# Sheet1.net
KiCad netlist of a schematic drawn in Altium Designer
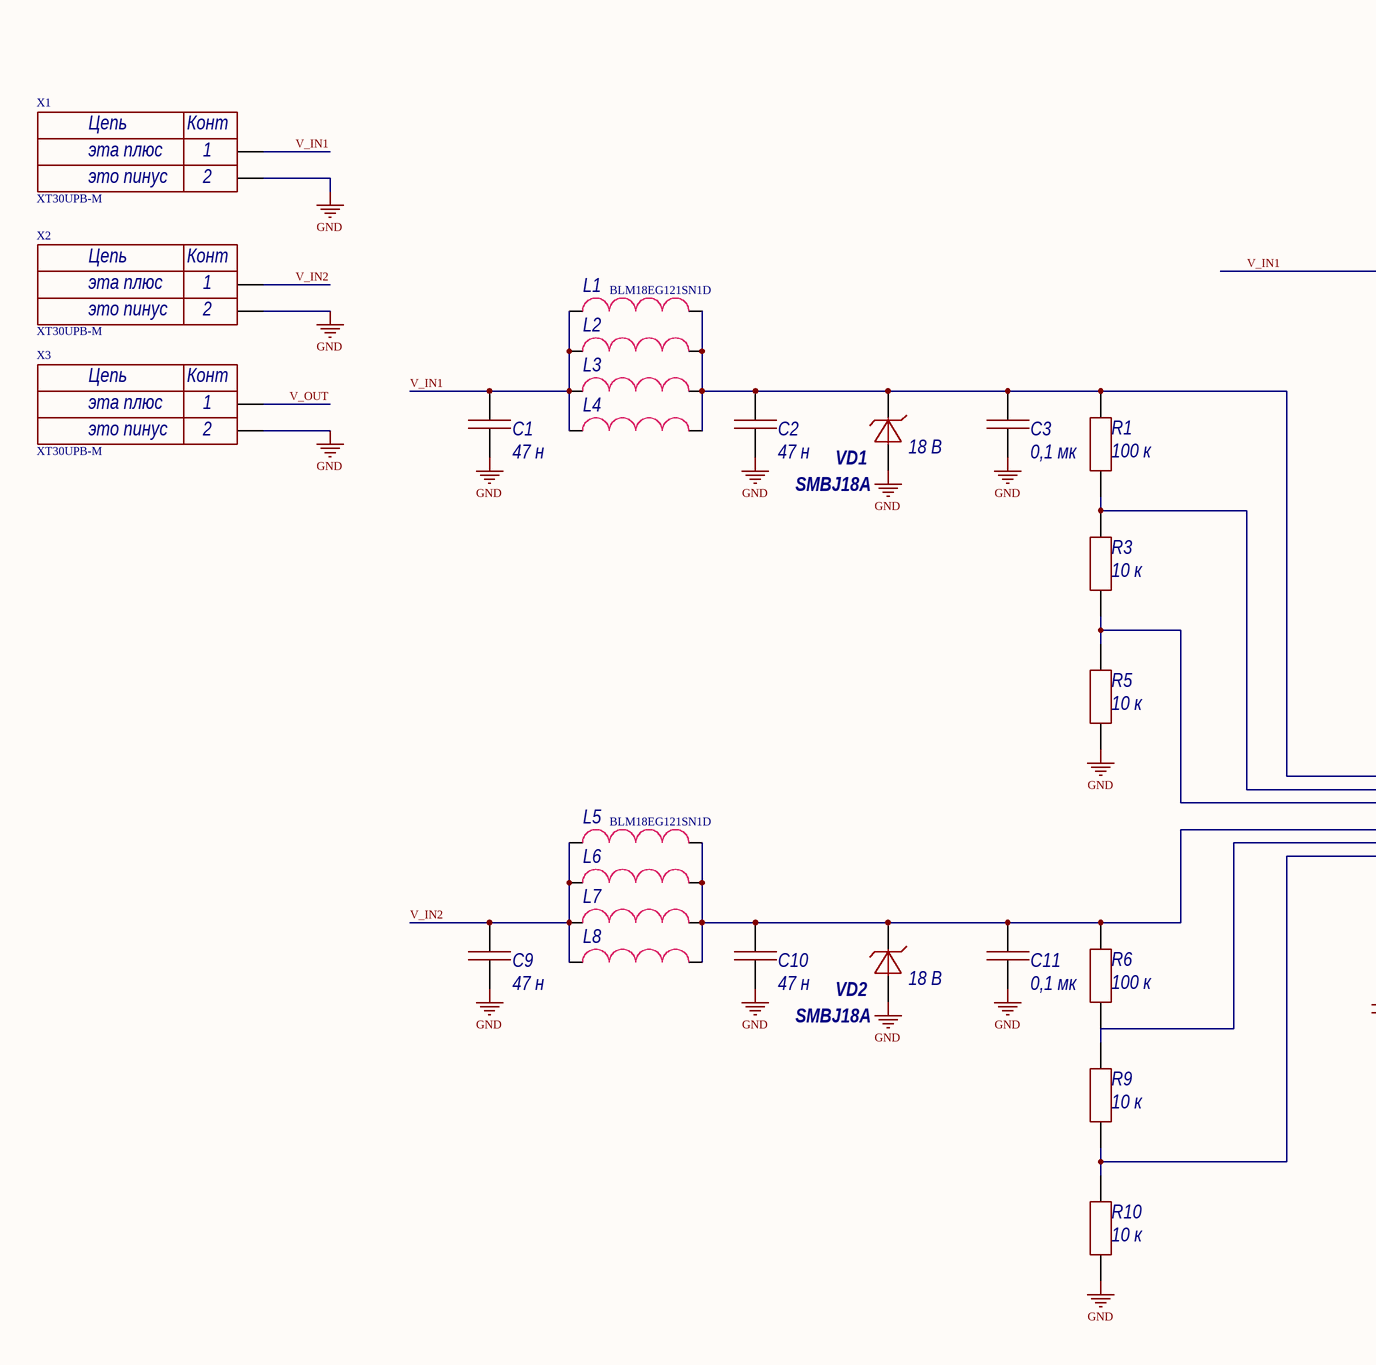
[diagram p0: Sheet1.SchDoc, left]
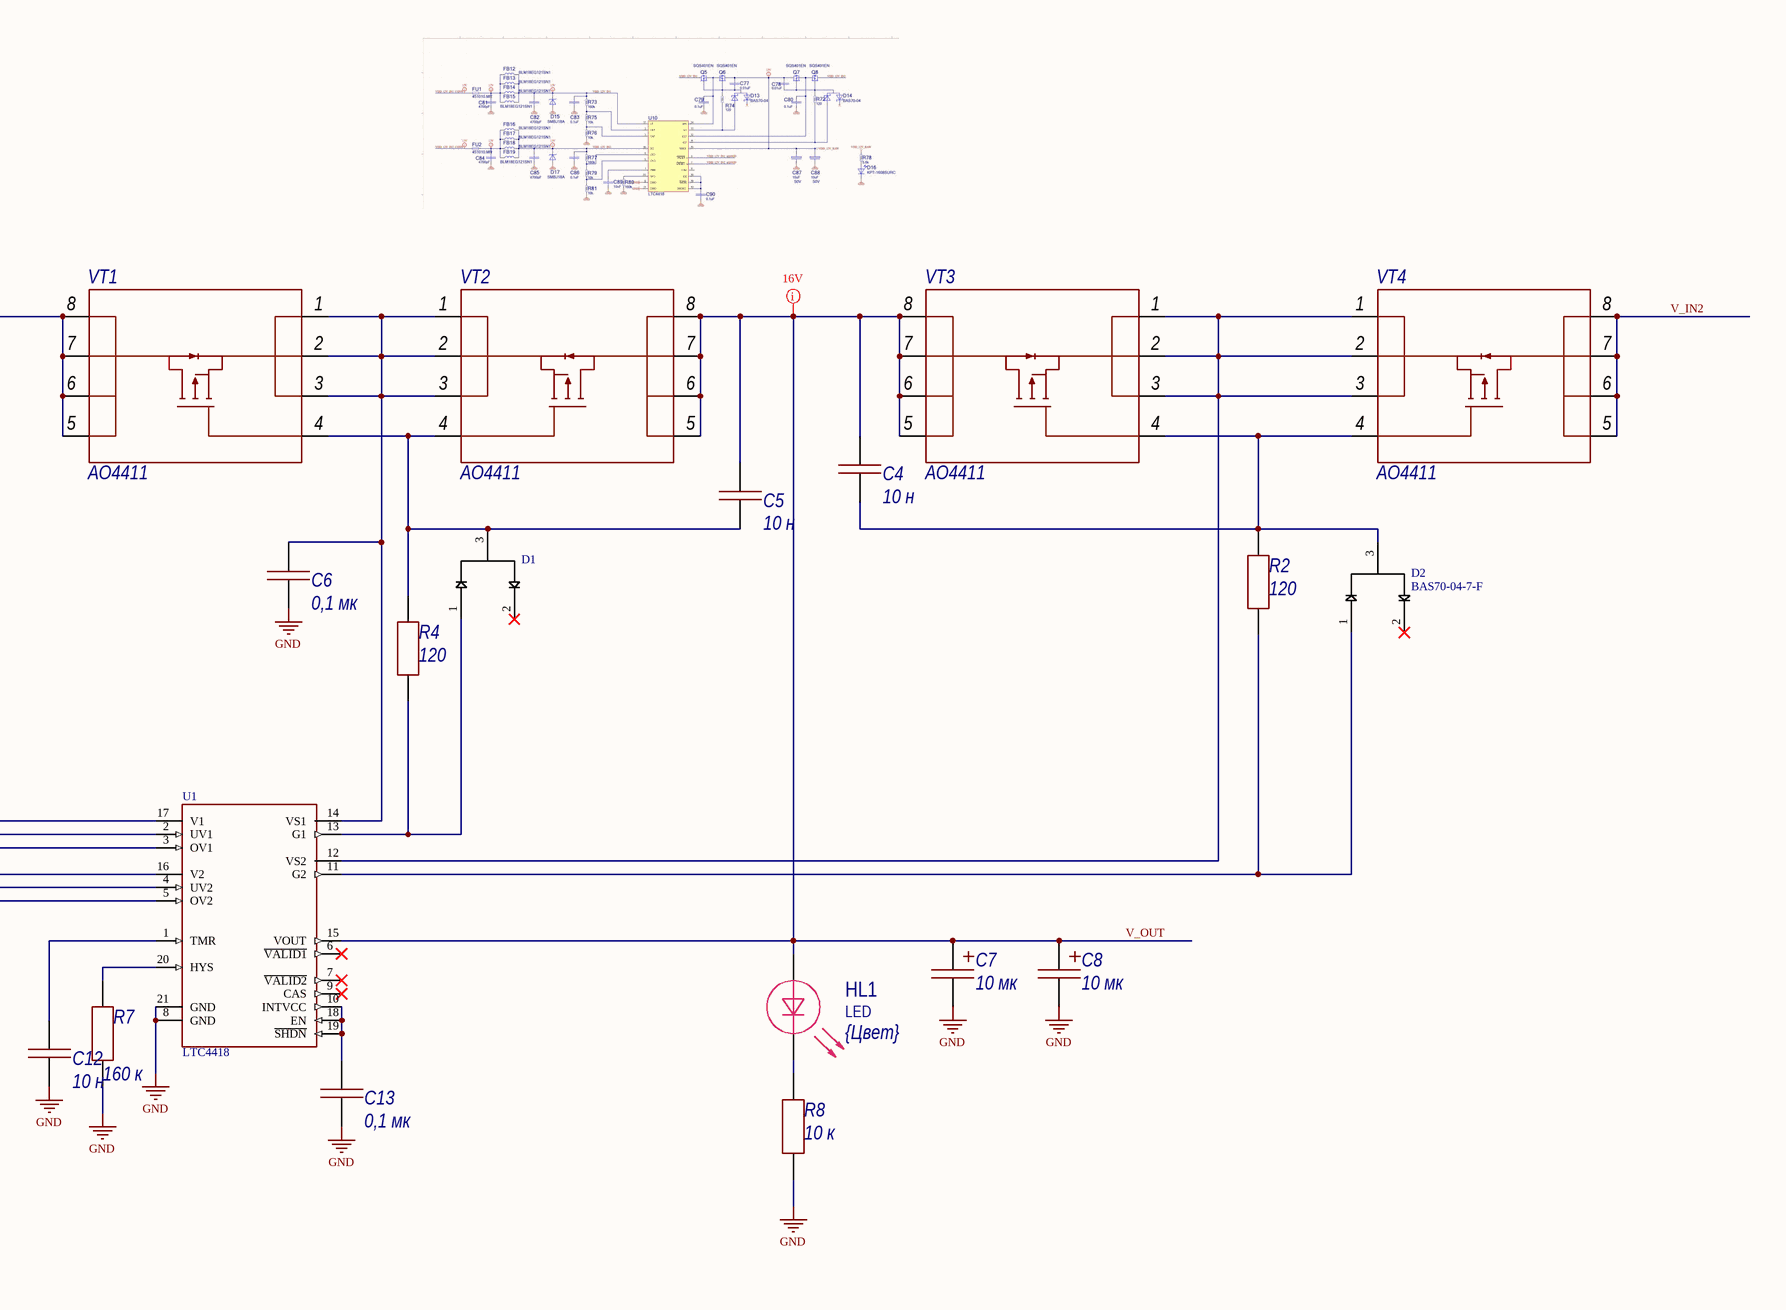
[diagram p1: Sheet1.SchDoc, right]

(export (version "E")
  (design (tool "Eeschema 10.0.6"))
  (components
    (comp (ref "C1")
      (value "47 н")
      (footprint "0603C")
      (description "Конденсатор")
      (fields (field (name "PART NUMBER") "Capacitor_47n_10_50V_X7R_0603C") (field (name "TOLERANCE") "0,1"))
      (libsource (lib "Hydrolib") (part "Capacitor"))
    )
    (comp (ref "C2")
      (value "47 н")
      (footprint "0603C")
      (description "Конденсатор")
      (fields (field (name "PART NUMBER") "Capacitor_47n_10_50V_X7R_0603C") (field (name "TOLERANCE") "0,1"))
      (libsource (lib "Hydrolib") (part "Capacitor"))
    )
    (comp (ref "C3")
      (value "0,1 мк")
      (footprint "0603C")
      (description "Конденсатор")
      (fields (field (name "PART NUMBER") "Capacitor_0,1u_10_50V_X7R_0603C") (field (name "TOLERANCE") "0,1"))
      (libsource (lib "Hydrolib") (part "Capacitor"))
    )
    (comp (ref "C4")
      (value "10 н")
      (footprint "0603C")
      (description "Конденсатор")
      (fields (field (name "PART NUMBER") "Capacitor_10n_10_50V_X7R_0603C") (field (name "TOLERANCE") "0,1"))
      (libsource (lib "Hydrolib") (part "Capacitor"))
    )
    (comp (ref "C5")
      (value "10 н")
      (footprint "0603C")
      (description "Конденсатор")
      (fields (field (name "PART NUMBER") "Capacitor_10n_10_50V_X7R_0603C") (field (name "TOLERANCE") "0,1"))
      (libsource (lib "Hydrolib") (part "Capacitor"))
    )
    (comp (ref "C6")
      (value "0,1 мк")
      (footprint "0603C")
      (description "Конденсатор")
      (fields (field (name "PART NUMBER") "Capacitor_0,1u_10_50V_X7R_0603C") (field (name "TOLERANCE") "0,1"))
      (libsource (lib "Hydrolib") (part "Capacitor"))
    )
    (comp (ref "C7")
      (value "10 мк")
      (footprint "TC_A")
      (description "Танталовый конденсатор")
      (fields (field (name "PART NUMBER") "Capacitor_10u_10_50V_TC_A") (field (name "TOLERANCE") "0,1"))
      (libsource (lib "Hydrolib") (part "Capacitor_polar"))
    )
    (comp (ref "C8")
      (value "10 мк")
      (footprint "TC_A")
      (description "Танталовый конденсатор")
      (fields (field (name "PART NUMBER") "Capacitor_10u_10_50V_TC_A") (field (name "TOLERANCE") "0,1"))
      (libsource (lib "Hydrolib") (part "Capacitor_polar"))
    )
    (comp (ref "C9")
      (value "47 н")
      (footprint "0603C")
      (description "Конденсатор")
      (fields (field (name "PART NUMBER") "Capacitor_47n_10_50V_X7R_0603C") (field (name "TOLERANCE") "0,1"))
      (libsource (lib "Hydrolib") (part "Capacitor"))
    )
    (comp (ref "C10")
      (value "47 н")
      (footprint "0603C")
      (description "Конденсатор")
      (fields (field (name "PART NUMBER") "Capacitor_47n_10_50V_X7R_0603C") (field (name "TOLERANCE") "0,1"))
      (libsource (lib "Hydrolib") (part "Capacitor"))
    )
    (comp (ref "C11")
      (value "0,1 мк")
      (footprint "0603C")
      (description "Конденсатор")
      (fields (field (name "PART NUMBER") "Capacitor_0,1u_10_50V_X7R_0603C") (field (name "TOLERANCE") "0,1"))
      (libsource (lib "Hydrolib") (part "Capacitor"))
    )
    (comp (ref "C12")
      (value "10 н")
      (footprint "0603C")
      (description "Конденсатор")
      (fields (field (name "PART NUMBER") "Capacitor_10n_10_50V_X7R_0603C") (field (name "TOLERANCE") "0,1"))
      (libsource (lib "Hydrolib") (part "Capacitor"))
    )
    (comp (ref "C13")
      (value "0,1 мк")
      (footprint "0603C")
      (description "Конденсатор")
      (fields (field (name "PART NUMBER") "Capacitor_0,1u_10_50V_X7R_0603C") (field (name "TOLERANCE") "0,1"))
      (libsource (lib "Hydrolib") (part "Capacitor"))
    )
    (comp (ref "D1")
      (value "~")
      (footprint "SOT23")
      (fields (field (name "MP") "BAS70-04-7-F") (field (name "MF") "Diodes Inc."))
      (libsource (lib "Hydrolib") (part "BAS70-04-7-F"))
    )
    (comp (ref "D2")
      (value "BAS70-04-7-F")
      (footprint "SOT23")
      (fields (field (name "MF") "Diodes Inc."))
      (libsource (lib "Hydrolib") (part "BAS70-04-7-F"))
    )
    (comp (ref "HL1")
      (value "LED")
      (footprint "0805D")
      (description "Светодиод")
      (fields (field (name "COLOR") "{Цвет}"))
      (libsource (lib "Hydrolib") (part "LED"))
    )
    (comp (ref "L1")
      (value "BLM18EG121SN1D")
      (footprint "0603L")
      (description "Катушка индуктивности")
      (fields (field (name "PART NUMBER") "Inductance"))
      (libsource (lib "Hydrolib") (part "Inductance"))
    )
    (comp (ref "L2")
      (value "Inductance")
      (footprint "0603L")
      (description "Катушка индуктивности")
      (libsource (lib "Hydrolib") (part "Inductance"))
    )
    (comp (ref "L3")
      (value "Inductance")
      (footprint "0603L")
      (description "Катушка индуктивности")
      (libsource (lib "Hydrolib") (part "Inductance"))
    )
    (comp (ref "L4")
      (value "Inductance")
      (footprint "0603L")
      (description "Катушка индуктивности")
      (libsource (lib "Hydrolib") (part "Inductance"))
    )
    (comp (ref "L5")
      (value "BLM18EG121SN1D")
      (footprint "0603L")
      (description "Катушка индуктивности")
      (fields (field (name "PART NUMBER") "Inductance"))
      (libsource (lib "Hydrolib") (part "Inductance"))
    )
    (comp (ref "L6")
      (value "Inductance")
      (footprint "0603L")
      (description "Катушка индуктивности")
      (libsource (lib "Hydrolib") (part "Inductance"))
    )
    (comp (ref "L7")
      (value "Inductance")
      (footprint "0603L")
      (description "Катушка индуктивности")
      (libsource (lib "Hydrolib") (part "Inductance"))
    )
    (comp (ref "L8")
      (value "Inductance")
      (footprint "0603L")
      (description "Катушка индуктивности")
      (libsource (lib "Hydrolib") (part "Inductance"))
    )
    (comp (ref "R1")
      (value "100 к")
      (footprint "0603R")
      (description "Резистор номиналом 100 кОм и точностью 1%")
      (fields (field (name "PART NUMBER") "Resistor_100k_1_0603") (field (name "TOLERANCE") "1%"))
      (libsource (lib "Hydrolib") (part "Resistor"))
    )
    (comp (ref "R2")
      (value "120")
      (footprint "0603R")
      (description "Резистор номиналом 120 Ом и точностью 1%")
      (fields (field (name "PART NUMBER") "Resistor_120_1_0603") (field (name "TOLERANCE") "1%"))
      (libsource (lib "Hydrolib") (part "Resistor"))
    )
    (comp (ref "R3")
      (value "10 к")
      (footprint "0603R")
      (description "Резистор номиналом 10 кОм и точностью 1%")
      (fields (field (name "PART NUMBER") "Resistor_10k_1_0603") (field (name "TOLERANCE") "1%"))
      (libsource (lib "Hydrolib") (part "Resistor"))
    )
    (comp (ref "R4")
      (value "120")
      (footprint "0603R")
      (description "Резистор номиналом 120 Ом и точностью 1%")
      (fields (field (name "PART NUMBER") "Resistor_120_1_0603") (field (name "TOLERANCE") "1%"))
      (libsource (lib "Hydrolib") (part "Resistor"))
    )
    (comp (ref "R5")
      (value "10 к")
      (footprint "0603R")
      (description "Резистор номиналом 10 кОм и точностью 1%")
      (fields (field (name "PART NUMBER") "Resistor_10k_1_0603") (field (name "TOLERANCE") "1%"))
      (libsource (lib "Hydrolib") (part "Resistor"))
    )
    (comp (ref "R6")
      (value "100 к")
      (footprint "0603R")
      (description "Резистор номиналом 100 кОм и точностью 1%")
      (fields (field (name "PART NUMBER") "Resistor_100k_1_0603") (field (name "TOLERANCE") "1%"))
      (libsource (lib "Hydrolib") (part "Resistor"))
    )
    (comp (ref "R7")
      (value "160 к")
      (footprint "0603R")
      (description "Резистор номиналом 160 кОм и точностью 1%")
      (fields (field (name "PART NUMBER") "Resistor_160k_1_0603") (field (name "TOLERANCE") "1%"))
      (libsource (lib "Hydrolib") (part "Resistor"))
    )
    (comp (ref "R8")
      (value "10 к")
      (footprint "0603R")
      (description "Резистор номиналом 10 кОм и точностью 1%")
      (fields (field (name "PART NUMBER") "Resistor_10k_1_0603") (field (name "TOLERANCE") "1%"))
      (libsource (lib "Hydrolib") (part "Resistor"))
    )
    (comp (ref "R9")
      (value "10 к")
      (footprint "0603R")
      (description "Резистор номиналом 10 кОм и точностью 1%")
      (fields (field (name "PART NUMBER") "Resistor_10k_1_0603") (field (name "TOLERANCE") "1%"))
      (libsource (lib "Hydrolib") (part "Resistor"))
    )
    (comp (ref "R10")
      (value "10 к")
      (footprint "0603R")
      (description "Резистор номиналом 10 кОм и точностью 1%")
      (fields (field (name "PART NUMBER") "Resistor_10k_1_0603") (field (name "TOLERANCE") "1%"))
      (libsource (lib "Hydrolib") (part "Resistor"))
    )
    (comp (ref "U1")
      (value "LTC4418")
      (footprint "QFN50")
      (fields (field (name "MF") "Analog Devices") (field (name "MP") "LTC4418IUF#PBF"))
      (libsource (lib "Hydrolib") (part "LTC4418"))
    )
    (comp (ref "VD1")
      (value "SMBJ18A")
      (footprint "SMB")
      (description "Защитный диод на 18 В, рассеиваемая мощность 600 Вт")
      (fields (field (name "ALTIUM_VALUE") "18 В"))
      (libsource (lib "Hydrolib") (part "TVS_1_1dir"))
    )
    (comp (ref "VD2")
      (value "SMBJ18A")
      (footprint "SMB")
      (description "Защитный диод на 18 В, рассеиваемая мощность 600 Вт")
      (fields (field (name "ALTIUM_VALUE") "18 В"))
      (libsource (lib "Hydrolib") (part "TVS_1_1dir"))
    )
    (comp (ref "VT1")
      (value "AO4411")
      (footprint "SOIC-8")
      (description "P-канальный MOSFET")
      (libsource (lib "") (part "MOSFET_P-channel_8pin_1"))
    )
    (comp (ref "VT2")
      (value "AO4411")
      (footprint "SOIC-8")
      (description "P-канальный MOSFET")
      (libsource (lib "Hydrolib") (part "MOSFET_P-channel_8pin"))
    )
    (comp (ref "VT3")
      (value "AO4411")
      (footprint "SOIC-8")
      (description "P-канальный MOSFET")
      (libsource (lib "") (part "MOSFET_P-channel_8pin_1"))
    )
    (comp (ref "VT4")
      (value "AO4411")
      (footprint "SOIC-8")
      (description "P-канальный MOSFET")
      (libsource (lib "Hydrolib") (part "MOSFET_P-channel_8pin"))
    )
    (comp (ref "X1")
      (value "XT30UPB-M")
      (footprint "XT30UPB-M")
      (description "2-пиновый разъем с ключом")
      (fields (field (name "VALUE2") "это пинус") (field (name "VALUE1") "эта плюс"))
      (libsource (lib "Hydrolib") (part "Polar_Conn"))
    )
    (comp (ref "X2")
      (value "XT30UPB-M")
      (footprint "XT30UPB-M")
      (description "2-пиновый разъем с ключом")
      (fields (field (name "VALUE2") "это пинус") (field (name "VALUE1") "эта плюс"))
      (libsource (lib "Hydrolib") (part "Polar_Conn"))
    )
    (comp (ref "X3")
      (value "XT30UPB-M")
      (footprint "XT30UPB-M")
      (description "2-пиновый разъем с ключом")
      (fields (field (name "VALUE2") "это пинус") (field (name "VALUE1") "эта плюс"))
      (libsource (lib "Hydrolib") (part "Polar_Conn"))
    )
  )
  (nets
    (net (code "1") (name "/V_IN1") (class "Default")
      (node (ref "C1") (pin "2") (pinfunction "2_2") (pintype "passive"))
      (node (ref "L1") (pin "1") (pinfunction "1_1") (pintype "passive"))
      (node (ref "L2") (pin "1") (pinfunction "1_1") (pintype "passive"))
      (node (ref "L3") (pin "1") (pinfunction "1_1") (pintype "passive"))
      (node (ref "L4") (pin "1") (pinfunction "1_1") (pintype "passive"))
      (node (ref "VT1") (pin "5") (pinfunction "5_5") (pintype "passive"))
      (node (ref "VT1") (pin "6") (pinfunction "6_6") (pintype "passive"))
      (node (ref "VT1") (pin "7") (pinfunction "7_7") (pintype "passive"))
      (node (ref "VT1") (pin "8") (pinfunction "8_8") (pintype "passive"))
      (node (ref "X1") (pin "P") (pinfunction "P_P") (pintype "passive"))
    )
    (net (code "2") (name "/V_IN2") (class "Default")
      (node (ref "C9") (pin "2") (pinfunction "2_2") (pintype "passive"))
      (node (ref "L5") (pin "1") (pinfunction "1_1") (pintype "passive"))
      (node (ref "L6") (pin "1") (pinfunction "1_1") (pintype "passive"))
      (node (ref "L7") (pin "1") (pinfunction "1_1") (pintype "passive"))
      (node (ref "L8") (pin "1") (pinfunction "1_1") (pintype "passive"))
      (node (ref "VT4") (pin "5") (pinfunction "5_5") (pintype "passive"))
      (node (ref "VT4") (pin "6") (pinfunction "6_6") (pintype "passive"))
      (node (ref "VT4") (pin "7") (pinfunction "7_7") (pintype "passive"))
      (node (ref "VT4") (pin "8") (pinfunction "8_8") (pintype "passive"))
      (node (ref "X2") (pin "P") (pinfunction "P_P") (pintype "passive"))
    )
    (net (code "3") (name "/V_OUT") (class "Default")
      (node (ref "C4") (pin "2") (pinfunction "2_2") (pintype "passive"))
      (node (ref "C5") (pin "2") (pinfunction "2_2") (pintype "passive"))
      (node (ref "C7") (pin "1") (pinfunction "1_1") (pintype "passive"))
      (node (ref "C8") (pin "1") (pinfunction "1_1") (pintype "passive"))
      (node (ref "HL1") (pin "1") (pinfunction "1_1") (pintype "passive"))
      (node (ref "U1") (pin "15") (pinfunction "VOUT_15") (pintype "output"))
      (node (ref "VT2") (pin "5") (pinfunction "5_5") (pintype "passive"))
      (node (ref "VT2") (pin "6") (pinfunction "6_6") (pintype "passive"))
      (node (ref "VT2") (pin "7") (pinfunction "7_7") (pintype "passive"))
      (node (ref "VT2") (pin "8") (pinfunction "8_8") (pintype "passive"))
      (node (ref "VT3") (pin "5") (pinfunction "5_5") (pintype "passive"))
      (node (ref "VT3") (pin "6") (pinfunction "6_6") (pintype "passive"))
      (node (ref "VT3") (pin "7") (pinfunction "7_7") (pintype "passive"))
      (node (ref "VT3") (pin "8") (pinfunction "8_8") (pintype "passive"))
      (node (ref "X3") (pin "P") (pinfunction "P_P") (pintype "passive"))
    )
    (net (code "4") (name "GND") (class "Default")
      (node (ref "C1") (pin "1") (pinfunction "1_1") (pintype "passive"))
      (node (ref "C10") (pin "1") (pinfunction "1_1") (pintype "passive"))
      (node (ref "C11") (pin "1") (pinfunction "1_1") (pintype "passive"))
      (node (ref "C12") (pin "1") (pinfunction "1_1") (pintype "passive"))
      (node (ref "C13") (pin "1") (pinfunction "1_1") (pintype "passive"))
      (node (ref "C2") (pin "1") (pinfunction "1_1") (pintype "passive"))
      (node (ref "C3") (pin "1") (pinfunction "1_1") (pintype "passive"))
      (node (ref "C6") (pin "1") (pinfunction "1_1") (pintype "passive"))
      (node (ref "C7") (pin "2") (pinfunction "2_2") (pintype "passive"))
      (node (ref "C8") (pin "2") (pinfunction "2_2") (pintype "passive"))
      (node (ref "C9") (pin "1") (pinfunction "1_1") (pintype "passive"))
      (node (ref "R10") (pin "1") (pinfunction "1_1") (pintype "passive"))
      (node (ref "R5") (pin "1") (pinfunction "1_1") (pintype "passive"))
      (node (ref "R7") (pin "1") (pinfunction "1_1") (pintype "passive"))
      (node (ref "R8") (pin "1") (pinfunction "1_1") (pintype "passive"))
      (node (ref "U1") (pin "21") (pinfunction "GND_21") (pintype "power_in"))
      (node (ref "U1") (pin "8") (pinfunction "GND_8") (pintype "power_in"))
      (node (ref "VD1") (pin "1") (pinfunction "1_1") (pintype "passive"))
      (node (ref "VD2") (pin "1") (pinfunction "1_1") (pintype "passive"))
      (node (ref "X1") (pin "N") (pinfunction "N_N") (pintype "passive"))
      (node (ref "X2") (pin "N") (pinfunction "N_N") (pintype "passive"))
      (node (ref "X3") (pin "N") (pinfunction "N_N") (pintype "passive"))
    )
    (net (code "5") (name "Net-(C4-Pad1)") (class "Default")
      (node (ref "C4") (pin "1") (pinfunction "1_1") (pintype "passive"))
      (node (ref "D2") (pin "3") (pinfunction "3_3") (pintype "passive"))
      (node (ref "R2") (pin "2") (pinfunction "2_2") (pintype "passive"))
      (node (ref "VT3") (pin "4") (pinfunction "4_4") (pintype "passive"))
      (node (ref "VT4") (pin "4") (pinfunction "4_4") (pintype "passive"))
    )
    (net (code "6") (name "Net-(C5-Pad1)") (class "Default")
      (node (ref "C5") (pin "1") (pinfunction "1_1") (pintype "passive"))
      (node (ref "D1") (pin "3") (pinfunction "3_3") (pintype "passive"))
      (node (ref "R4") (pin "2") (pinfunction "2_2") (pintype "passive"))
      (node (ref "VT1") (pin "4") (pinfunction "4_4") (pintype "passive"))
      (node (ref "VT2") (pin "4") (pinfunction "4_4") (pintype "passive"))
    )
    (net (code "7") (name "Net-(HL1-Pad2)") (class "Default")
      (node (ref "HL1") (pin "2") (pinfunction "2_2") (pintype "passive"))
      (node (ref "R8") (pin "2") (pinfunction "2_2") (pintype "passive"))
    )
    (net (code "8") (name "Net-(U1-EN)") (class "Default")
      (node (ref "C13") (pin "2") (pinfunction "2_2") (pintype "passive"))
      (node (ref "U1") (pin "10") (pinfunction "INTVCC_10") (pintype "output"))
      (node (ref "U1") (pin "18") (pinfunction "EN_18") (pintype "input"))
      (node (ref "U1") (pin "19") (pinfunction "~{SHDN}_19") (pintype "input"))
    )
    (net (code "9") (name "Net-(U1-G1)") (class "Default")
      (node (ref "D1") (pin "1") (pinfunction "1_1") (pintype "passive"))
      (node (ref "R4") (pin "1") (pinfunction "1_1") (pintype "passive"))
      (node (ref "U1") (pin "13") (pinfunction "G1_13") (pintype "output"))
    )
    (net (code "10") (name "Net-(U1-G2)") (class "Default")
      (node (ref "D2") (pin "1") (pinfunction "1_1") (pintype "passive"))
      (node (ref "R2") (pin "1") (pinfunction "1_1") (pintype "passive"))
      (node (ref "U1") (pin "11") (pinfunction "G2_11") (pintype "output"))
    )
    (net (code "11") (name "Net-(U1-HYS)") (class "Default")
      (node (ref "R7") (pin "2") (pinfunction "2_2") (pintype "passive"))
      (node (ref "U1") (pin "20") (pinfunction "HYS_20") (pintype "input"))
    )
    (net (code "12") (name "Net-(U1-OV1)") (class "Default")
      (node (ref "R3") (pin "1") (pinfunction "1_1") (pintype "passive"))
      (node (ref "R5") (pin "2") (pinfunction "2_2") (pintype "passive"))
      (node (ref "U1") (pin "3") (pinfunction "OV1_3") (pintype "input"))
    )
    (net (code "13") (name "Net-(U1-OV2)") (class "Default")
      (node (ref "R10") (pin "2") (pinfunction "2_2") (pintype "passive"))
      (node (ref "R9") (pin "1") (pinfunction "1_1") (pintype "passive"))
      (node (ref "U1") (pin "5") (pinfunction "OV2_5") (pintype "input"))
    )
    (net (code "14") (name "Net-(U1-TMR)") (class "Default")
      (node (ref "C12") (pin "2") (pinfunction "2_2") (pintype "passive"))
      (node (ref "U1") (pin "1") (pinfunction "TMR_1") (pintype "input"))
    )
    (net (code "15") (name "Net-(U1-UV1)") (class "Default")
      (node (ref "R1") (pin "1") (pinfunction "1_1") (pintype "passive"))
      (node (ref "R3") (pin "2") (pinfunction "2_2") (pintype "passive"))
      (node (ref "U1") (pin "2") (pinfunction "UV1_2") (pintype "input"))
    )
    (net (code "16") (name "Net-(U1-UV2)") (class "Default")
      (node (ref "R6") (pin "1") (pinfunction "1_1") (pintype "passive"))
      (node (ref "R9") (pin "2") (pinfunction "2_2") (pintype "passive"))
      (node (ref "U1") (pin "4") (pinfunction "UV2_4") (pintype "input"))
    )
    (net (code "17") (name "Net-(U1-V1)") (class "Default")
      (node (ref "C2") (pin "2") (pinfunction "2_2") (pintype "passive"))
      (node (ref "C3") (pin "2") (pinfunction "2_2") (pintype "passive"))
      (node (ref "L1") (pin "2") (pinfunction "2_2") (pintype "passive"))
      (node (ref "L2") (pin "2") (pinfunction "2_2") (pintype "passive"))
      (node (ref "L3") (pin "2") (pinfunction "2_2") (pintype "passive"))
      (node (ref "L4") (pin "2") (pinfunction "2_2") (pintype "passive"))
      (node (ref "R1") (pin "2") (pinfunction "2_2") (pintype "passive"))
      (node (ref "U1") (pin "17") (pinfunction "V1_17") (pintype "power_in"))
      (node (ref "VD1") (pin "2") (pinfunction "2_2") (pintype "passive"))
    )
    (net (code "18") (name "Net-(U1-V2)") (class "Default")
      (node (ref "C10") (pin "2") (pinfunction "2_2") (pintype "passive"))
      (node (ref "C11") (pin "2") (pinfunction "2_2") (pintype "passive"))
      (node (ref "L5") (pin "2") (pinfunction "2_2") (pintype "passive"))
      (node (ref "L6") (pin "2") (pinfunction "2_2") (pintype "passive"))
      (node (ref "L7") (pin "2") (pinfunction "2_2") (pintype "passive"))
      (node (ref "L8") (pin "2") (pinfunction "2_2") (pintype "passive"))
      (node (ref "R6") (pin "2") (pinfunction "2_2") (pintype "passive"))
      (node (ref "U1") (pin "16") (pinfunction "V2_16") (pintype "power_in"))
      (node (ref "VD2") (pin "2") (pinfunction "2_2") (pintype "passive"))
    )
    (net (code "19") (name "Net-(U1-VS1)") (class "Default")
      (node (ref "C6") (pin "2") (pinfunction "2_2") (pintype "passive"))
      (node (ref "U1") (pin "14") (pinfunction "VS1_14") (pintype "power_in"))
      (node (ref "VT1") (pin "1") (pinfunction "1_1") (pintype "passive"))
      (node (ref "VT1") (pin "2") (pinfunction "2_2") (pintype "passive"))
      (node (ref "VT1") (pin "3") (pinfunction "3_3") (pintype "passive"))
      (node (ref "VT2") (pin "1") (pinfunction "1_1") (pintype "passive"))
      (node (ref "VT2") (pin "2") (pinfunction "2_2") (pintype "passive"))
      (node (ref "VT2") (pin "3") (pinfunction "3_3") (pintype "passive"))
    )
    (net (code "20") (name "Net-(U1-VS2)") (class "Default")
      (node (ref "U1") (pin "12") (pinfunction "VS2_12") (pintype "power_in"))
      (node (ref "VT3") (pin "1") (pinfunction "1_1") (pintype "passive"))
      (node (ref "VT3") (pin "2") (pinfunction "2_2") (pintype "passive"))
      (node (ref "VT3") (pin "3") (pinfunction "3_3") (pintype "passive"))
      (node (ref "VT4") (pin "1") (pinfunction "1_1") (pintype "passive"))
      (node (ref "VT4") (pin "2") (pinfunction "2_2") (pintype "passive"))
      (node (ref "VT4") (pin "3") (pinfunction "3_3") (pintype "passive"))
    )
    (net (code "21") (name "unconnected-(D1-Pad2)") (class "Default")
      (node (ref "D1") (pin "2") (pinfunction "2_2") (pintype "passive+no_connect"))
    )
    (net (code "22") (name "unconnected-(D2-Pad2)") (class "Default")
      (node (ref "D2") (pin "2") (pinfunction "2_2") (pintype "passive+no_connect"))
    )
    (net (code "23") (name "unconnected-(U1-CAS-Pad9)") (class "Default")
      (node (ref "U1") (pin "9") (pinfunction "CAS_9") (pintype "output+no_connect"))
    )
    (net (code "24") (name "unconnected-(U1-~{VALID1}-Pad6)") (class "Default")
      (node (ref "U1") (pin "6") (pinfunction "~{VALID1}_6") (pintype "output+no_connect"))
    )
    (net (code "25") (name "unconnected-(U1-~{VALID2}-Pad7)") (class "Default")
      (node (ref "U1") (pin "7") (pinfunction "~{VALID2}_7") (pintype "output+no_connect"))
    )
  )
)
